# hot-plate_heater_v1_0.net
KiCad netlist of a schematic drawn in EAGLE
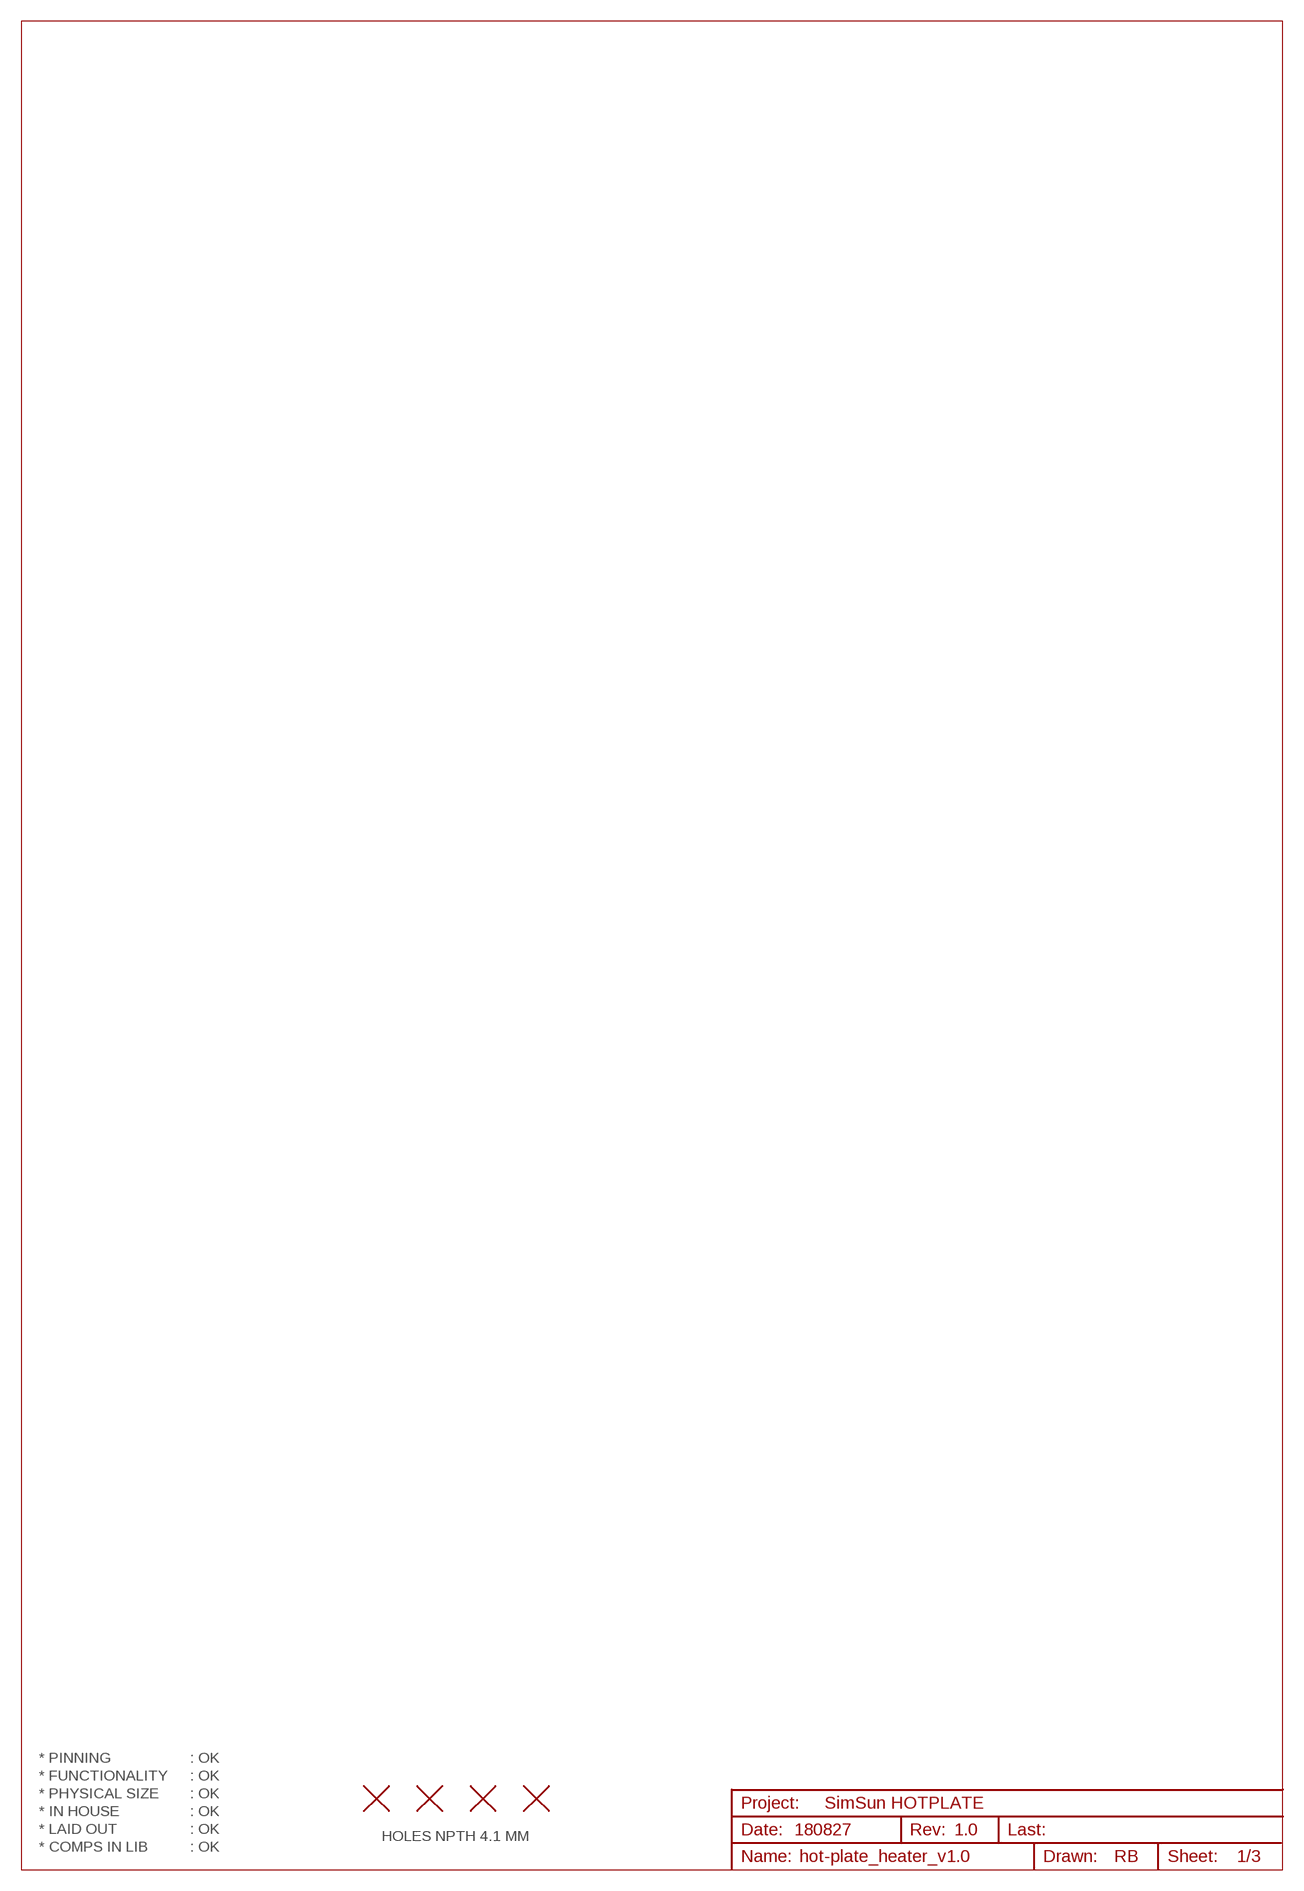
[diagram p0: schematic, sheet 1]
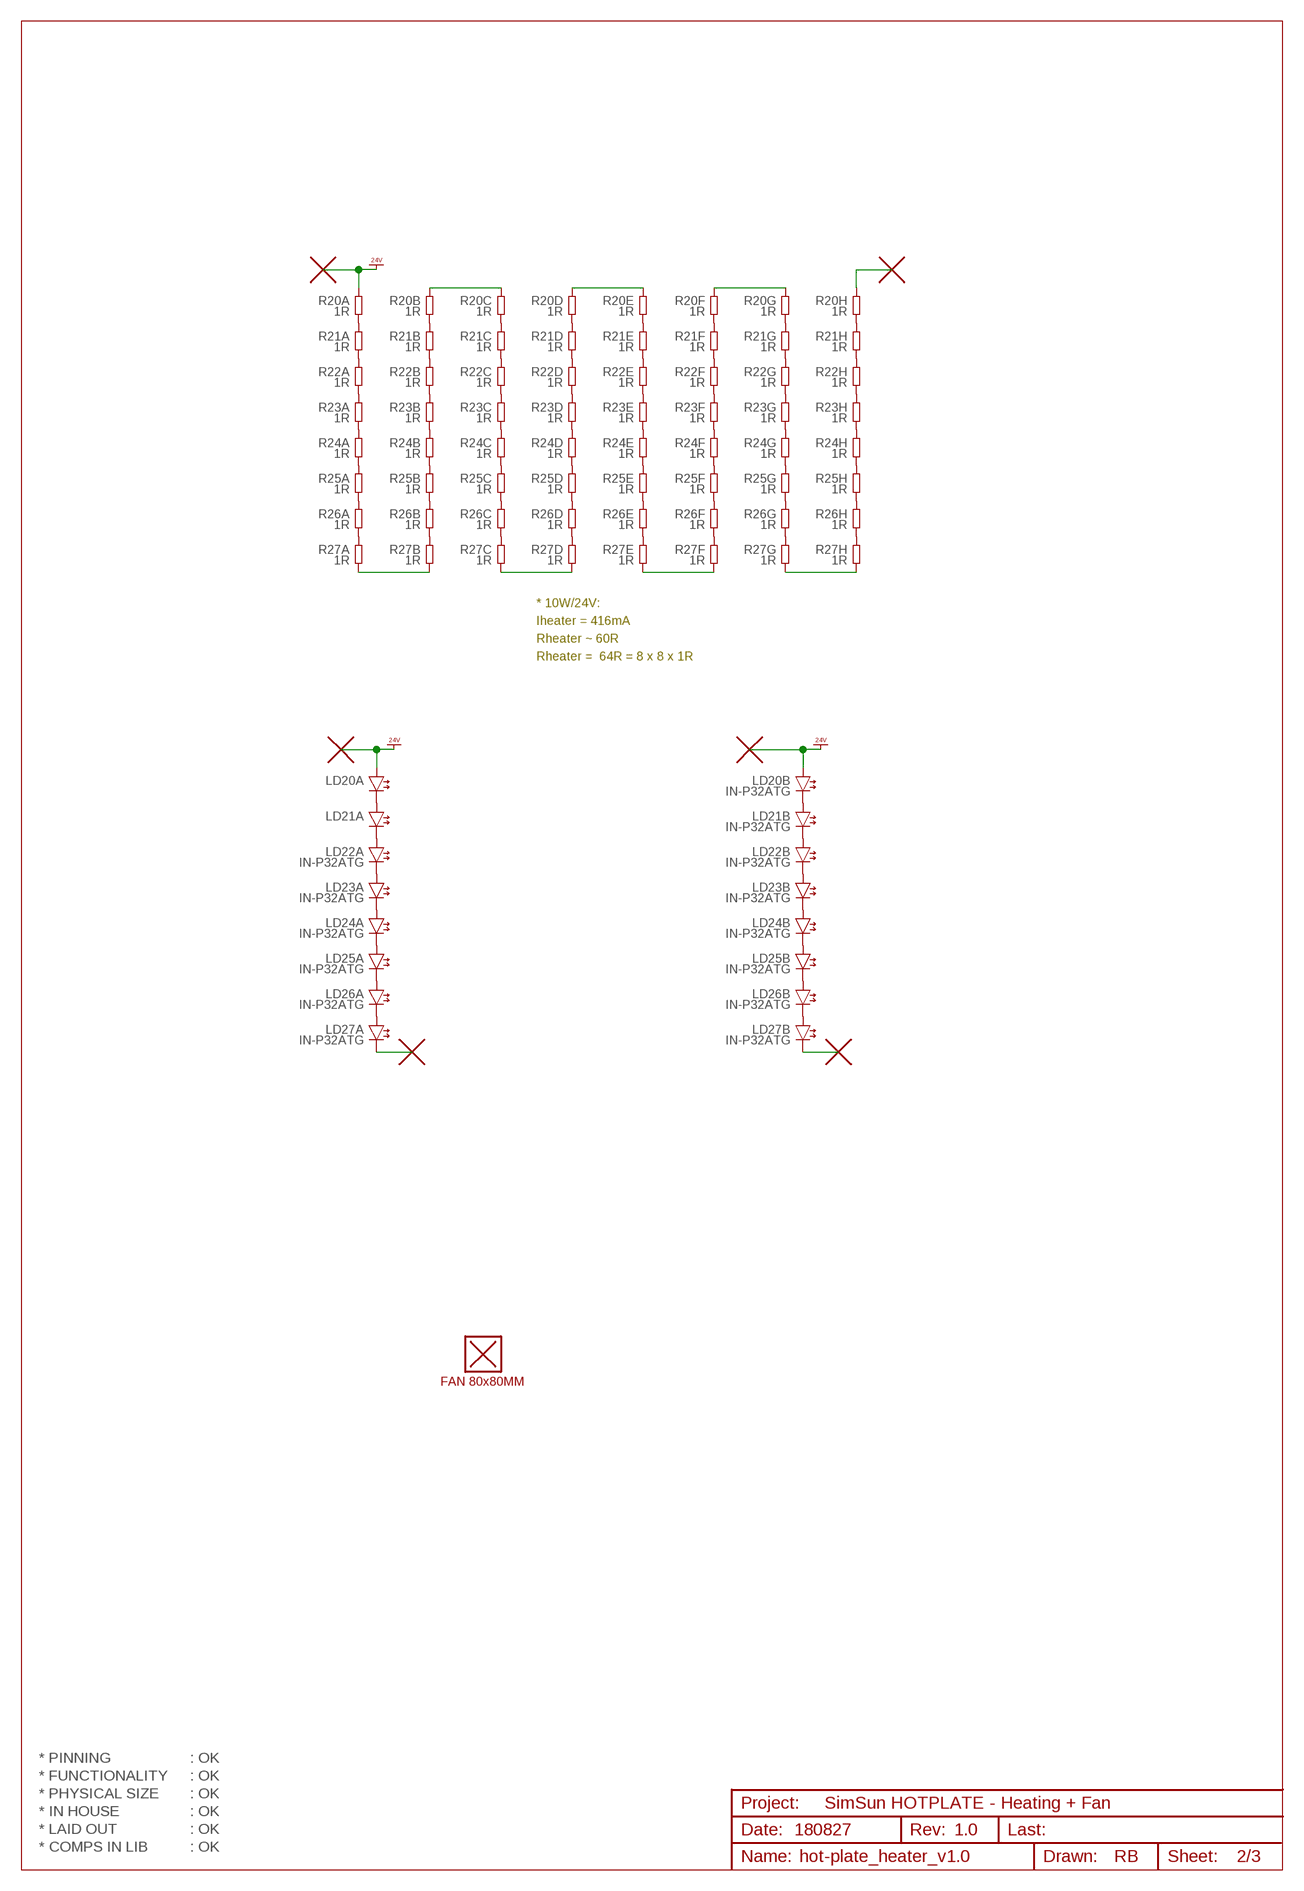
[diagram p1: schematic, sheet 2]
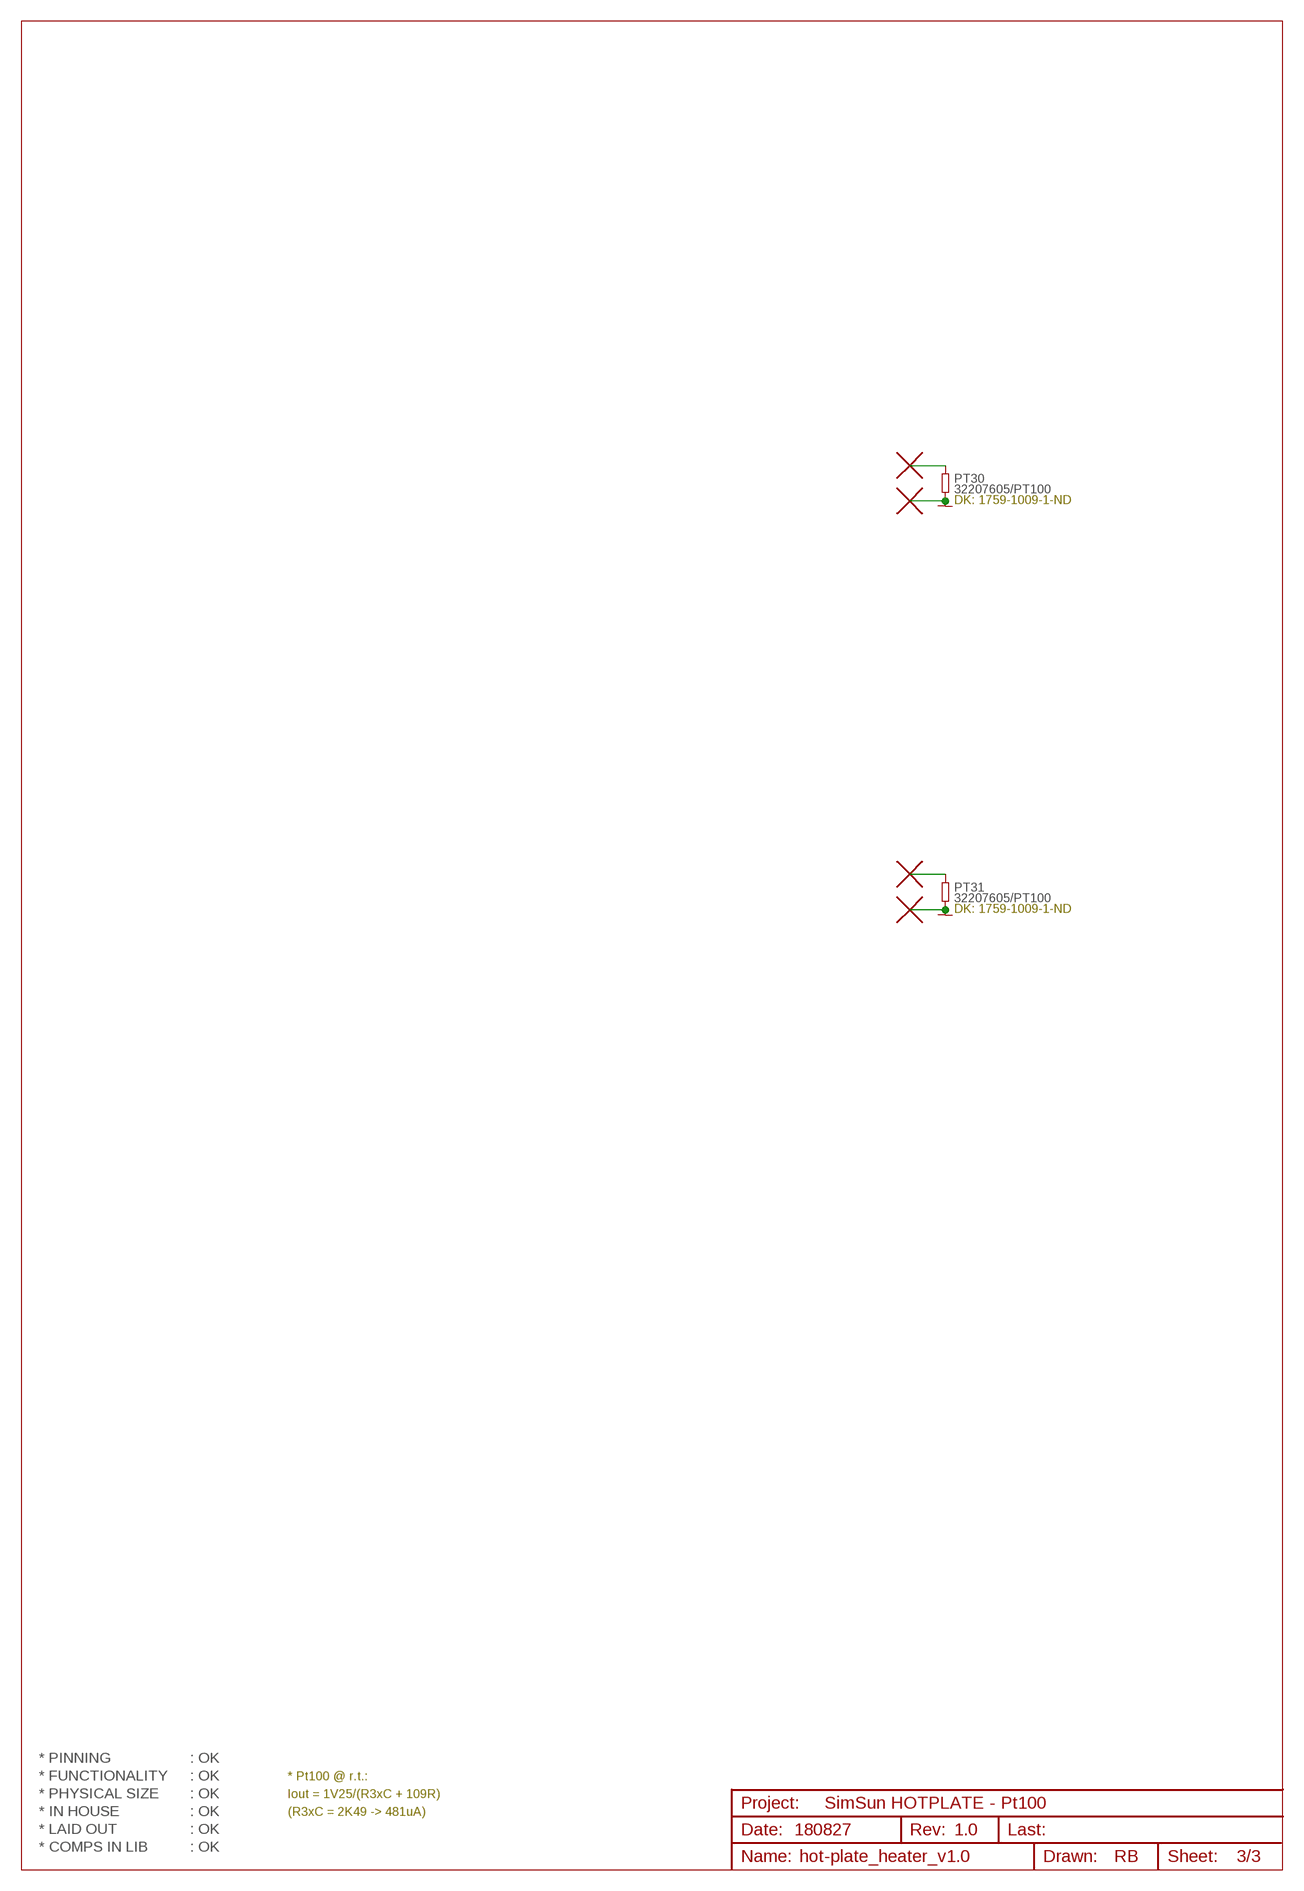
[diagram p2: schematic, sheet 3]

(export (version "E")
  (design (tool "Eeschema 10.0.6"))
  (components
    (comp (ref "H1")
      (value "HOLE_NPTH_4.1MM")
      (footprint "eagle-import:HOLE_NPTH_4.1MM")
      (libsource (lib "eagle-import") (part "HOLE_NPTH_4.1MM"))
    )
    (comp (ref "H2")
      (value "HOLE_NPTH_4.1MM")
      (footprint "eagle-import:HOLE_NPTH_4.1MM")
      (libsource (lib "eagle-import") (part "HOLE_NPTH_4.1MM"))
    )
    (comp (ref "H3")
      (value "HOLE_NPTH_4.1MM")
      (footprint "eagle-import:HOLE_NPTH_4.1MM")
      (libsource (lib "eagle-import") (part "HOLE_NPTH_4.1MM"))
    )
    (comp (ref "H4")
      (value "HOLE_NPTH_4.1MM")
      (footprint "eagle-import:HOLE_NPTH_4.1MM")
      (libsource (lib "eagle-import") (part "HOLE_NPTH_4.1MM"))
    )
    (comp (ref "H24")
      (value "PAD_ROUND_3.2MM")
      (footprint "eagle-import:PAD_ROUND_3.2MM")
      (libsource (lib "eagle-import") (part "PAD_ROUND_3.2MM"))
    )
    (comp (ref "H25")
      (value "PAD_ROUND_3.2MM")
      (footprint "eagle-import:PAD_ROUND_3.2MM")
      (libsource (lib "eagle-import") (part "PAD_ROUND_3.2MM"))
    )
    (comp (ref "H26")
      (value "PAD_ROUND_3.2MM")
      (footprint "eagle-import:PAD_ROUND_3.2MM")
      (libsource (lib "eagle-import") (part "PAD_ROUND_3.2MM"))
    )
    (comp (ref "H27")
      (value "PAD_ROUND_3.2MM")
      (footprint "eagle-import:PAD_ROUND_3.2MM")
      (libsource (lib "eagle-import") (part "PAD_ROUND_3.2MM"))
    )
    (comp (ref "PT30")
      (value "32207605/PT100")
      (footprint "eagle-import:RES0805")
      (libsource (lib "eagle-import") (part "RES0805"))
    )
    (comp (ref "PT31")
      (value "32207605/PT100")
      (footprint "eagle-import:RES0805")
      (libsource (lib "eagle-import") (part "RES0805"))
    )
    (comp (ref "H9")
      (value "FAN_80X80MM_SANYO_SANACE80")
      (footprint "eagle-import:FAN_80X80MM_SANYO_SANACE80")
      (libsource (lib "eagle-import") (part "FAN_80X80MM_SANYO_SANACE80"))
    )
    (comp (ref "H18")
      (value "PAD_ROUND_3.2MM")
      (footprint "eagle-import:PAD_ROUND_3.2MM")
      (libsource (lib "eagle-import") (part "PAD_ROUND_3.2MM"))
    )
    (comp (ref "H19")
      (value "PAD_ROUND_3.2MM")
      (footprint "eagle-import:PAD_ROUND_3.2MM")
      (libsource (lib "eagle-import") (part "PAD_ROUND_3.2MM"))
    )
    (comp (ref "H20")
      (value "PAD_ROUND_3.2MM")
      (footprint "eagle-import:PAD_ROUND_3.2MM")
      (libsource (lib "eagle-import") (part "PAD_ROUND_3.2MM"))
    )
    (comp (ref "H21")
      (value "PAD_ROUND_3.2MM")
      (footprint "eagle-import:PAD_ROUND_3.2MM")
      (libsource (lib "eagle-import") (part "PAD_ROUND_3.2MM"))
    )
    (comp (ref "H22")
      (value "PAD_ROUND_3.2MM")
      (footprint "eagle-import:PAD_ROUND_3.2MM")
      (libsource (lib "eagle-import") (part "PAD_ROUND_3.2MM"))
    )
    (comp (ref "H23")
      (value "PAD_ROUND_3.2MM")
      (footprint "eagle-import:PAD_ROUND_3.2MM")
      (libsource (lib "eagle-import") (part "PAD_ROUND_3.2MM"))
    )
    (comp (ref "LD20A")
      (value "IN-P32ATG")
      (footprint "eagle-import:LED_SMD_PLCC2")
      (libsource (lib "eagle-import") (part "LED_SMD_PLCC2"))
    )
    (comp (ref "LD20B")
      (value "IN-P32ATG")
      (footprint "eagle-import:LED_SMD_PLCC2")
      (libsource (lib "eagle-import") (part "LED_SMD_PLCC2"))
    )
    (comp (ref "LD21A")
      (value "IN-P32ATG")
      (footprint "eagle-import:LED_SMD_PLCC2")
      (libsource (lib "eagle-import") (part "LED_SMD_PLCC2"))
    )
    (comp (ref "LD21B")
      (value "IN-P32ATG")
      (footprint "eagle-import:LED_SMD_PLCC2")
      (libsource (lib "eagle-import") (part "LED_SMD_PLCC2"))
    )
    (comp (ref "LD22A")
      (value "IN-P32ATG")
      (footprint "eagle-import:LED_SMD_PLCC2")
      (libsource (lib "eagle-import") (part "LED_SMD_PLCC2"))
    )
    (comp (ref "LD22B")
      (value "IN-P32ATG")
      (footprint "eagle-import:LED_SMD_PLCC2")
      (libsource (lib "eagle-import") (part "LED_SMD_PLCC2"))
    )
    (comp (ref "LD23A")
      (value "IN-P32ATG")
      (footprint "eagle-import:LED_SMD_PLCC2")
      (libsource (lib "eagle-import") (part "LED_SMD_PLCC2"))
    )
    (comp (ref "LD23B")
      (value "IN-P32ATG")
      (footprint "eagle-import:LED_SMD_PLCC2")
      (libsource (lib "eagle-import") (part "LED_SMD_PLCC2"))
    )
    (comp (ref "LD24A")
      (value "IN-P32ATG")
      (footprint "eagle-import:LED_SMD_PLCC2")
      (libsource (lib "eagle-import") (part "LED_SMD_PLCC2"))
    )
    (comp (ref "LD24B")
      (value "IN-P32ATG")
      (footprint "eagle-import:LED_SMD_PLCC2")
      (libsource (lib "eagle-import") (part "LED_SMD_PLCC2"))
    )
    (comp (ref "LD25A")
      (value "IN-P32ATG")
      (footprint "eagle-import:LED_SMD_PLCC2")
      (libsource (lib "eagle-import") (part "LED_SMD_PLCC2"))
    )
    (comp (ref "LD25B")
      (value "IN-P32ATG")
      (footprint "eagle-import:LED_SMD_PLCC2")
      (libsource (lib "eagle-import") (part "LED_SMD_PLCC2"))
    )
    (comp (ref "LD26A")
      (value "IN-P32ATG")
      (footprint "eagle-import:LED_SMD_PLCC2")
      (libsource (lib "eagle-import") (part "LED_SMD_PLCC2"))
    )
    (comp (ref "LD26B")
      (value "IN-P32ATG")
      (footprint "eagle-import:LED_SMD_PLCC2")
      (libsource (lib "eagle-import") (part "LED_SMD_PLCC2"))
    )
    (comp (ref "LD27A")
      (value "IN-P32ATG")
      (footprint "eagle-import:LED_SMD_PLCC2")
      (libsource (lib "eagle-import") (part "LED_SMD_PLCC2"))
    )
    (comp (ref "LD27B")
      (value "IN-P32ATG")
      (footprint "eagle-import:LED_SMD_PLCC2")
      (libsource (lib "eagle-import") (part "LED_SMD_PLCC2"))
    )
    (comp (ref "R20A")
      (value "1R")
      (footprint "eagle-import:RES2512")
      (libsource (lib "eagle-import") (part "RES2512"))
    )
    (comp (ref "R20B")
      (value "1R")
      (footprint "eagle-import:RES2512")
      (libsource (lib "eagle-import") (part "RES2512"))
    )
    (comp (ref "R20C")
      (value "1R")
      (footprint "eagle-import:RES2512")
      (libsource (lib "eagle-import") (part "RES2512"))
    )
    (comp (ref "R20D")
      (value "1R")
      (footprint "eagle-import:RES2512")
      (libsource (lib "eagle-import") (part "RES2512"))
    )
    (comp (ref "R20E")
      (value "1R")
      (footprint "eagle-import:RES2512")
      (libsource (lib "eagle-import") (part "RES2512"))
    )
    (comp (ref "R20F")
      (value "1R")
      (footprint "eagle-import:RES2512")
      (libsource (lib "eagle-import") (part "RES2512"))
    )
    (comp (ref "R20G")
      (value "1R")
      (footprint "eagle-import:RES2512")
      (libsource (lib "eagle-import") (part "RES2512"))
    )
    (comp (ref "R20H")
      (value "1R")
      (footprint "eagle-import:RES2512")
      (libsource (lib "eagle-import") (part "RES2512"))
    )
    (comp (ref "R21A")
      (value "1R")
      (footprint "eagle-import:RES2512")
      (libsource (lib "eagle-import") (part "RES2512"))
    )
    (comp (ref "R21B")
      (value "1R")
      (footprint "eagle-import:RES2512")
      (libsource (lib "eagle-import") (part "RES2512"))
    )
    (comp (ref "R21C")
      (value "1R")
      (footprint "eagle-import:RES2512")
      (libsource (lib "eagle-import") (part "RES2512"))
    )
    (comp (ref "R21D")
      (value "1R")
      (footprint "eagle-import:RES2512")
      (libsource (lib "eagle-import") (part "RES2512"))
    )
    (comp (ref "R21E")
      (value "1R")
      (footprint "eagle-import:RES2512")
      (libsource (lib "eagle-import") (part "RES2512"))
    )
    (comp (ref "R21F")
      (value "1R")
      (footprint "eagle-import:RES2512")
      (libsource (lib "eagle-import") (part "RES2512"))
    )
    (comp (ref "R21G")
      (value "1R")
      (footprint "eagle-import:RES2512")
      (libsource (lib "eagle-import") (part "RES2512"))
    )
    (comp (ref "R21H")
      (value "1R")
      (footprint "eagle-import:RES2512")
      (libsource (lib "eagle-import") (part "RES2512"))
    )
    (comp (ref "R22A")
      (value "1R")
      (footprint "eagle-import:RES2512")
      (libsource (lib "eagle-import") (part "RES2512"))
    )
    (comp (ref "R22B")
      (value "1R")
      (footprint "eagle-import:RES2512")
      (libsource (lib "eagle-import") (part "RES2512"))
    )
    (comp (ref "R22C")
      (value "1R")
      (footprint "eagle-import:RES2512")
      (libsource (lib "eagle-import") (part "RES2512"))
    )
    (comp (ref "R22D")
      (value "1R")
      (footprint "eagle-import:RES2512")
      (libsource (lib "eagle-import") (part "RES2512"))
    )
    (comp (ref "R22E")
      (value "1R")
      (footprint "eagle-import:RES2512")
      (libsource (lib "eagle-import") (part "RES2512"))
    )
    (comp (ref "R22F")
      (value "1R")
      (footprint "eagle-import:RES2512")
      (libsource (lib "eagle-import") (part "RES2512"))
    )
    (comp (ref "R22G")
      (value "1R")
      (footprint "eagle-import:RES2512")
      (libsource (lib "eagle-import") (part "RES2512"))
    )
    (comp (ref "R22H")
      (value "1R")
      (footprint "eagle-import:RES2512")
      (libsource (lib "eagle-import") (part "RES2512"))
    )
    (comp (ref "R23A")
      (value "1R")
      (footprint "eagle-import:RES2512")
      (libsource (lib "eagle-import") (part "RES2512"))
    )
    (comp (ref "R23B")
      (value "1R")
      (footprint "eagle-import:RES2512")
      (libsource (lib "eagle-import") (part "RES2512"))
    )
    (comp (ref "R23C")
      (value "1R")
      (footprint "eagle-import:RES2512")
      (libsource (lib "eagle-import") (part "RES2512"))
    )
    (comp (ref "R23D")
      (value "1R")
      (footprint "eagle-import:RES2512")
      (libsource (lib "eagle-import") (part "RES2512"))
    )
    (comp (ref "R23E")
      (value "1R")
      (footprint "eagle-import:RES2512")
      (libsource (lib "eagle-import") (part "RES2512"))
    )
    (comp (ref "R23F")
      (value "1R")
      (footprint "eagle-import:RES2512")
      (libsource (lib "eagle-import") (part "RES2512"))
    )
    (comp (ref "R23G")
      (value "1R")
      (footprint "eagle-import:RES2512")
      (libsource (lib "eagle-import") (part "RES2512"))
    )
    (comp (ref "R23H")
      (value "1R")
      (footprint "eagle-import:RES2512")
      (libsource (lib "eagle-import") (part "RES2512"))
    )
    (comp (ref "R24A")
      (value "1R")
      (footprint "eagle-import:RES2512")
      (libsource (lib "eagle-import") (part "RES2512"))
    )
    (comp (ref "R24B")
      (value "1R")
      (footprint "eagle-import:RES2512")
      (libsource (lib "eagle-import") (part "RES2512"))
    )
    (comp (ref "R24C")
      (value "1R")
      (footprint "eagle-import:RES2512")
      (libsource (lib "eagle-import") (part "RES2512"))
    )
    (comp (ref "R24D")
      (value "1R")
      (footprint "eagle-import:RES2512")
      (libsource (lib "eagle-import") (part "RES2512"))
    )
    (comp (ref "R24E")
      (value "1R")
      (footprint "eagle-import:RES2512")
      (libsource (lib "eagle-import") (part "RES2512"))
    )
    (comp (ref "R24F")
      (value "1R")
      (footprint "eagle-import:RES2512")
      (libsource (lib "eagle-import") (part "RES2512"))
    )
    (comp (ref "R24G")
      (value "1R")
      (footprint "eagle-import:RES2512")
      (libsource (lib "eagle-import") (part "RES2512"))
    )
    (comp (ref "R24H")
      (value "1R")
      (footprint "eagle-import:RES2512")
      (libsource (lib "eagle-import") (part "RES2512"))
    )
    (comp (ref "R25A")
      (value "1R")
      (footprint "eagle-import:RES2512")
      (libsource (lib "eagle-import") (part "RES2512"))
    )
    (comp (ref "R25B")
      (value "1R")
      (footprint "eagle-import:RES2512")
      (libsource (lib "eagle-import") (part "RES2512"))
    )
    (comp (ref "R25C")
      (value "1R")
      (footprint "eagle-import:RES2512")
      (libsource (lib "eagle-import") (part "RES2512"))
    )
    (comp (ref "R25D")
      (value "1R")
      (footprint "eagle-import:RES2512")
      (libsource (lib "eagle-import") (part "RES2512"))
    )
    (comp (ref "R25E")
      (value "1R")
      (footprint "eagle-import:RES2512")
      (libsource (lib "eagle-import") (part "RES2512"))
    )
    (comp (ref "R25F")
      (value "1R")
      (footprint "eagle-import:RES2512")
      (libsource (lib "eagle-import") (part "RES2512"))
    )
    (comp (ref "R25G")
      (value "1R")
      (footprint "eagle-import:RES2512")
      (libsource (lib "eagle-import") (part "RES2512"))
    )
    (comp (ref "R25H")
      (value "1R")
      (footprint "eagle-import:RES2512")
      (libsource (lib "eagle-import") (part "RES2512"))
    )
    (comp (ref "R26A")
      (value "1R")
      (footprint "eagle-import:RES2512")
      (libsource (lib "eagle-import") (part "RES2512"))
    )
    (comp (ref "R26B")
      (value "1R")
      (footprint "eagle-import:RES2512")
      (libsource (lib "eagle-import") (part "RES2512"))
    )
    (comp (ref "R26C")
      (value "1R")
      (footprint "eagle-import:RES2512")
      (libsource (lib "eagle-import") (part "RES2512"))
    )
    (comp (ref "R26D")
      (value "1R")
      (footprint "eagle-import:RES2512")
      (libsource (lib "eagle-import") (part "RES2512"))
    )
    (comp (ref "R26E")
      (value "1R")
      (footprint "eagle-import:RES2512")
      (libsource (lib "eagle-import") (part "RES2512"))
    )
    (comp (ref "R26F")
      (value "1R")
      (footprint "eagle-import:RES2512")
      (libsource (lib "eagle-import") (part "RES2512"))
    )
    (comp (ref "R26G")
      (value "1R")
      (footprint "eagle-import:RES2512")
      (libsource (lib "eagle-import") (part "RES2512"))
    )
    (comp (ref "R26H")
      (value "1R")
      (footprint "eagle-import:RES2512")
      (libsource (lib "eagle-import") (part "RES2512"))
    )
    (comp (ref "R27A")
      (value "1R")
      (footprint "eagle-import:RES2512")
      (libsource (lib "eagle-import") (part "RES2512"))
    )
    (comp (ref "R27B")
      (value "1R")
      (footprint "eagle-import:RES2512")
      (libsource (lib "eagle-import") (part "RES2512"))
    )
    (comp (ref "R27C")
      (value "1R")
      (footprint "eagle-import:RES2512")
      (libsource (lib "eagle-import") (part "RES2512"))
    )
    (comp (ref "R27D")
      (value "1R")
      (footprint "eagle-import:RES2512")
      (libsource (lib "eagle-import") (part "RES2512"))
    )
    (comp (ref "R27E")
      (value "1R")
      (footprint "eagle-import:RES2512")
      (libsource (lib "eagle-import") (part "RES2512"))
    )
    (comp (ref "R27F")
      (value "1R")
      (footprint "eagle-import:RES2512")
      (libsource (lib "eagle-import") (part "RES2512"))
    )
    (comp (ref "R27G")
      (value "1R")
      (footprint "eagle-import:RES2512")
      (libsource (lib "eagle-import") (part "RES2512"))
    )
    (comp (ref "R27H")
      (value "1R")
      (footprint "eagle-import:RES2512")
      (libsource (lib "eagle-import") (part "RES2512"))
    )
  )
  (nets
    (net (code "1") (name "GND") (class "Default")
      (node (ref "H25") (pin "P") (pinfunction "P_P") (pintype "bidirectional"))
      (node (ref "H27") (pin "P") (pinfunction "P_P") (pintype "bidirectional"))
      (node (ref "PT30") (pin "2") (pinfunction "2_2") (pintype "passive"))
      (node (ref "PT31") (pin "2") (pinfunction "2_2") (pintype "passive"))
    )
    (net (code "2") (name "Net-(H19-PadP)") (class "Default")
      (node (ref "H19") (pin "P") (pinfunction "P_P") (pintype "bidirectional"))
      (node (ref "R20H") (pin "1") (pinfunction "1_1") (pintype "passive"))
    )
    (net (code "3") (name "Net-(H24-PadP)") (class "Default")
      (node (ref "H24") (pin "P") (pinfunction "P_P") (pintype "bidirectional"))
      (node (ref "PT30") (pin "1") (pinfunction "1_1") (pintype "passive"))
    )
    (net (code "4") (name "Net-(H26-PadP)") (class "Default")
      (node (ref "H26") (pin "P") (pinfunction "P_P") (pintype "bidirectional"))
      (node (ref "PT31") (pin "1") (pinfunction "1_1") (pintype "passive"))
    )
    (net (code "5") (name "Net-(LD20A--)") (class "Default")
      (node (ref "LD20A") (pin "C") (pinfunction "-_C") (pintype "passive"))
      (node (ref "LD21A") (pin "A") (pinfunction "+_A") (pintype "passive"))
    )
    (net (code "6") (name "Net-(LD20B--)") (class "Default")
      (node (ref "LD20B") (pin "C") (pinfunction "-_C") (pintype "passive"))
      (node (ref "LD21B") (pin "A") (pinfunction "+_A") (pintype "passive"))
    )
    (net (code "7") (name "Net-(LD21A--)") (class "Default")
      (node (ref "LD21A") (pin "C") (pinfunction "-_C") (pintype "passive"))
      (node (ref "LD22A") (pin "A") (pinfunction "+_A") (pintype "passive"))
    )
    (net (code "8") (name "Net-(LD21B--)") (class "Default")
      (node (ref "LD21B") (pin "C") (pinfunction "-_C") (pintype "passive"))
      (node (ref "LD22B") (pin "A") (pinfunction "+_A") (pintype "passive"))
    )
    (net (code "9") (name "Net-(LD22A--)") (class "Default")
      (node (ref "LD22A") (pin "C") (pinfunction "-_C") (pintype "passive"))
      (node (ref "LD23A") (pin "A") (pinfunction "+_A") (pintype "passive"))
    )
    (net (code "10") (name "Net-(LD22B--)") (class "Default")
      (node (ref "LD22B") (pin "C") (pinfunction "-_C") (pintype "passive"))
      (node (ref "LD23B") (pin "A") (pinfunction "+_A") (pintype "passive"))
    )
    (net (code "11") (name "Net-(LD23A--)") (class "Default")
      (node (ref "LD23A") (pin "C") (pinfunction "-_C") (pintype "passive"))
      (node (ref "LD24A") (pin "A") (pinfunction "+_A") (pintype "passive"))
    )
    (net (code "12") (name "Net-(LD23B--)") (class "Default")
      (node (ref "LD23B") (pin "C") (pinfunction "-_C") (pintype "passive"))
      (node (ref "LD24B") (pin "A") (pinfunction "+_A") (pintype "passive"))
    )
    (net (code "13") (name "Net-(LD24A--)") (class "Default")
      (node (ref "LD24A") (pin "C") (pinfunction "-_C") (pintype "passive"))
      (node (ref "LD25A") (pin "A") (pinfunction "+_A") (pintype "passive"))
    )
    (net (code "14") (name "Net-(LD24B--)") (class "Default")
      (node (ref "LD24B") (pin "C") (pinfunction "-_C") (pintype "passive"))
      (node (ref "LD25B") (pin "A") (pinfunction "+_A") (pintype "passive"))
    )
    (net (code "15") (name "Net-(LD25A--)") (class "Default")
      (node (ref "LD25A") (pin "C") (pinfunction "-_C") (pintype "passive"))
      (node (ref "LD26A") (pin "A") (pinfunction "+_A") (pintype "passive"))
    )
    (net (code "16") (name "Net-(LD25B--)") (class "Default")
      (node (ref "LD25B") (pin "C") (pinfunction "-_C") (pintype "passive"))
      (node (ref "LD26B") (pin "A") (pinfunction "+_A") (pintype "passive"))
    )
    (net (code "17") (name "Net-(LD26A--)") (class "Default")
      (node (ref "LD26A") (pin "C") (pinfunction "-_C") (pintype "passive"))
      (node (ref "LD27A") (pin "A") (pinfunction "+_A") (pintype "passive"))
    )
    (net (code "18") (name "Net-(LD26B--)") (class "Default")
      (node (ref "LD26B") (pin "C") (pinfunction "-_C") (pintype "passive"))
      (node (ref "LD27B") (pin "A") (pinfunction "+_A") (pintype "passive"))
    )
    (net (code "19") (name "Net-(LD27A--)") (class "Default")
      (node (ref "H22") (pin "P") (pinfunction "P_P") (pintype "bidirectional"))
      (node (ref "LD27A") (pin "C") (pinfunction "-_C") (pintype "passive"))
    )
    (net (code "20") (name "Net-(LD27B--)") (class "Default")
      (node (ref "H23") (pin "P") (pinfunction "P_P") (pintype "bidirectional"))
      (node (ref "LD27B") (pin "C") (pinfunction "-_C") (pintype "passive"))
    )
    (net (code "21") (name "Net-(R20A-Pad2)") (class "Default")
      (node (ref "R20A") (pin "2") (pinfunction "2_2") (pintype "passive"))
      (node (ref "R21A") (pin "1") (pinfunction "1_1") (pintype "passive"))
    )
    (net (code "22") (name "Net-(R20B-Pad1)") (class "Default")
      (node (ref "R20B") (pin "1") (pinfunction "1_1") (pintype "passive"))
      (node (ref "R20C") (pin "1") (pinfunction "1_1") (pintype "passive"))
    )
    (net (code "23") (name "Net-(R20B-Pad2)") (class "Default")
      (node (ref "R20B") (pin "2") (pinfunction "2_2") (pintype "passive"))
      (node (ref "R21B") (pin "1") (pinfunction "1_1") (pintype "passive"))
    )
    (net (code "24") (name "Net-(R20C-Pad2)") (class "Default")
      (node (ref "R20C") (pin "2") (pinfunction "2_2") (pintype "passive"))
      (node (ref "R21C") (pin "1") (pinfunction "1_1") (pintype "passive"))
    )
    (net (code "25") (name "Net-(R20D-Pad1)") (class "Default")
      (node (ref "R20D") (pin "1") (pinfunction "1_1") (pintype "passive"))
      (node (ref "R20E") (pin "1") (pinfunction "1_1") (pintype "passive"))
    )
    (net (code "26") (name "Net-(R20D-Pad2)") (class "Default")
      (node (ref "R20D") (pin "2") (pinfunction "2_2") (pintype "passive"))
      (node (ref "R21D") (pin "1") (pinfunction "1_1") (pintype "passive"))
    )
    (net (code "27") (name "Net-(R20E-Pad2)") (class "Default")
      (node (ref "R20E") (pin "2") (pinfunction "2_2") (pintype "passive"))
      (node (ref "R21E") (pin "1") (pinfunction "1_1") (pintype "passive"))
    )
    (net (code "28") (name "Net-(R20F-Pad1)") (class "Default")
      (node (ref "R20F") (pin "1") (pinfunction "1_1") (pintype "passive"))
      (node (ref "R20G") (pin "1") (pinfunction "1_1") (pintype "passive"))
    )
    (net (code "29") (name "Net-(R20F-Pad2)") (class "Default")
      (node (ref "R20F") (pin "2") (pinfunction "2_2") (pintype "passive"))
      (node (ref "R21F") (pin "1") (pinfunction "1_1") (pintype "passive"))
    )
    (net (code "30") (name "Net-(R20G-Pad2)") (class "Default")
      (node (ref "R20G") (pin "2") (pinfunction "2_2") (pintype "passive"))
      (node (ref "R21G") (pin "1") (pinfunction "1_1") (pintype "passive"))
    )
    (net (code "31") (name "Net-(R20H-Pad2)") (class "Default")
      (node (ref "R20H") (pin "2") (pinfunction "2_2") (pintype "passive"))
      (node (ref "R21H") (pin "1") (pinfunction "1_1") (pintype "passive"))
    )
    (net (code "32") (name "Net-(R21A-Pad2)") (class "Default")
      (node (ref "R21A") (pin "2") (pinfunction "2_2") (pintype "passive"))
      (node (ref "R22A") (pin "1") (pinfunction "1_1") (pintype "passive"))
    )
    (net (code "33") (name "Net-(R21B-Pad2)") (class "Default")
      (node (ref "R21B") (pin "2") (pinfunction "2_2") (pintype "passive"))
      (node (ref "R22B") (pin "1") (pinfunction "1_1") (pintype "passive"))
    )
    (net (code "34") (name "Net-(R21C-Pad2)") (class "Default")
      (node (ref "R21C") (pin "2") (pinfunction "2_2") (pintype "passive"))
      (node (ref "R22C") (pin "1") (pinfunction "1_1") (pintype "passive"))
    )
    (net (code "35") (name "Net-(R21D-Pad2)") (class "Default")
      (node (ref "R21D") (pin "2") (pinfunction "2_2") (pintype "passive"))
      (node (ref "R22D") (pin "1") (pinfunction "1_1") (pintype "passive"))
    )
    (net (code "36") (name "Net-(R21E-Pad2)") (class "Default")
      (node (ref "R21E") (pin "2") (pinfunction "2_2") (pintype "passive"))
      (node (ref "R22E") (pin "1") (pinfunction "1_1") (pintype "passive"))
    )
    (net (code "37") (name "Net-(R21F-Pad2)") (class "Default")
      (node (ref "R21F") (pin "2") (pinfunction "2_2") (pintype "passive"))
      (node (ref "R22F") (pin "1") (pinfunction "1_1") (pintype "passive"))
    )
    (net (code "38") (name "Net-(R21G-Pad2)") (class "Default")
      (node (ref "R21G") (pin "2") (pinfunction "2_2") (pintype "passive"))
      (node (ref "R22G") (pin "1") (pinfunction "1_1") (pintype "passive"))
    )
    (net (code "39") (name "Net-(R21H-Pad2)") (class "Default")
      (node (ref "R21H") (pin "2") (pinfunction "2_2") (pintype "passive"))
      (node (ref "R22H") (pin "1") (pinfunction "1_1") (pintype "passive"))
    )
    (net (code "40") (name "Net-(R22A-Pad2)") (class "Default")
      (node (ref "R22A") (pin "2") (pinfunction "2_2") (pintype "passive"))
      (node (ref "R23A") (pin "1") (pinfunction "1_1") (pintype "passive"))
    )
    (net (code "41") (name "Net-(R22B-Pad2)") (class "Default")
      (node (ref "R22B") (pin "2") (pinfunction "2_2") (pintype "passive"))
      (node (ref "R23B") (pin "1") (pinfunction "1_1") (pintype "passive"))
    )
    (net (code "42") (name "Net-(R22C-Pad2)") (class "Default")
      (node (ref "R22C") (pin "2") (pinfunction "2_2") (pintype "passive"))
      (node (ref "R23C") (pin "1") (pinfunction "1_1") (pintype "passive"))
    )
    (net (code "43") (name "Net-(R22D-Pad2)") (class "Default")
      (node (ref "R22D") (pin "2") (pinfunction "2_2") (pintype "passive"))
      (node (ref "R23D") (pin "1") (pinfunction "1_1") (pintype "passive"))
    )
    (net (code "44") (name "Net-(R22E-Pad2)") (class "Default")
      (node (ref "R22E") (pin "2") (pinfunction "2_2") (pintype "passive"))
      (node (ref "R23E") (pin "1") (pinfunction "1_1") (pintype "passive"))
    )
    (net (code "45") (name "Net-(R22F-Pad2)") (class "Default")
      (node (ref "R22F") (pin "2") (pinfunction "2_2") (pintype "passive"))
      (node (ref "R23F") (pin "1") (pinfunction "1_1") (pintype "passive"))
    )
    (net (code "46") (name "Net-(R22G-Pad2)") (class "Default")
      (node (ref "R22G") (pin "2") (pinfunction "2_2") (pintype "passive"))
      (node (ref "R23G") (pin "1") (pinfunction "1_1") (pintype "passive"))
    )
    (net (code "47") (name "Net-(R22H-Pad2)") (class "Default")
      (node (ref "R22H") (pin "2") (pinfunction "2_2") (pintype "passive"))
      (node (ref "R23H") (pin "1") (pinfunction "1_1") (pintype "passive"))
    )
    (net (code "48") (name "Net-(R23A-Pad2)") (class "Default")
      (node (ref "R23A") (pin "2") (pinfunction "2_2") (pintype "passive"))
      (node (ref "R24A") (pin "1") (pinfunction "1_1") (pintype "passive"))
    )
    (net (code "49") (name "Net-(R23B-Pad2)") (class "Default")
      (node (ref "R23B") (pin "2") (pinfunction "2_2") (pintype "passive"))
      (node (ref "R24B") (pin "1") (pinfunction "1_1") (pintype "passive"))
    )
    (net (code "50") (name "Net-(R23C-Pad2)") (class "Default")
      (node (ref "R23C") (pin "2") (pinfunction "2_2") (pintype "passive"))
      (node (ref "R24C") (pin "1") (pinfunction "1_1") (pintype "passive"))
    )
    (net (code "51") (name "Net-(R23D-Pad2)") (class "Default")
      (node (ref "R23D") (pin "2") (pinfunction "2_2") (pintype "passive"))
      (node (ref "R24D") (pin "1") (pinfunction "1_1") (pintype "passive"))
    )
    (net (code "52") (name "Net-(R23E-Pad2)") (class "Default")
      (node (ref "R23E") (pin "2") (pinfunction "2_2") (pintype "passive"))
      (node (ref "R24E") (pin "1") (pinfunction "1_1") (pintype "passive"))
    )
    (net (code "53") (name "Net-(R23F-Pad2)") (class "Default")
      (node (ref "R23F") (pin "2") (pinfunction "2_2") (pintype "passive"))
      (node (ref "R24F") (pin "1") (pinfunction "1_1") (pintype "passive"))
    )
    (net (code "54") (name "Net-(R23G-Pad2)") (class "Default")
      (node (ref "R23G") (pin "2") (pinfunction "2_2") (pintype "passive"))
      (node (ref "R24G") (pin "1") (pinfunction "1_1") (pintype "passive"))
    )
    (net (code "55") (name "Net-(R23H-Pad2)") (class "Default")
      (node (ref "R23H") (pin "2") (pinfunction "2_2") (pintype "passive"))
      (node (ref "R24H") (pin "1") (pinfunction "1_1") (pintype "passive"))
    )
    (net (code "56") (name "Net-(R24A-Pad2)") (class "Default")
      (node (ref "R24A") (pin "2") (pinfunction "2_2") (pintype "passive"))
      (node (ref "R25A") (pin "1") (pinfunction "1_1") (pintype "passive"))
    )
    (net (code "57") (name "Net-(R24B-Pad2)") (class "Default")
      (node (ref "R24B") (pin "2") (pinfunction "2_2") (pintype "passive"))
      (node (ref "R25B") (pin "1") (pinfunction "1_1") (pintype "passive"))
    )
    (net (code "58") (name "Net-(R24C-Pad2)") (class "Default")
      (node (ref "R24C") (pin "2") (pinfunction "2_2") (pintype "passive"))
      (node (ref "R25C") (pin "1") (pinfunction "1_1") (pintype "passive"))
    )
    (net (code "59") (name "Net-(R24D-Pad2)") (class "Default")
      (node (ref "R24D") (pin "2") (pinfunction "2_2") (pintype "passive"))
      (node (ref "R25D") (pin "1") (pinfunction "1_1") (pintype "passive"))
    )
    (net (code "60") (name "Net-(R24E-Pad2)") (class "Default")
      (node (ref "R24E") (pin "2") (pinfunction "2_2") (pintype "passive"))
      (node (ref "R25E") (pin "1") (pinfunction "1_1") (pintype "passive"))
    )
    (net (code "61") (name "Net-(R24F-Pad2)") (class "Default")
      (node (ref "R24F") (pin "2") (pinfunction "2_2") (pintype "passive"))
      (node (ref "R25F") (pin "1") (pinfunction "1_1") (pintype "passive"))
    )
    (net (code "62") (name "Net-(R24G-Pad2)") (class "Default")
      (node (ref "R24G") (pin "2") (pinfunction "2_2") (pintype "passive"))
      (node (ref "R25G") (pin "1") (pinfunction "1_1") (pintype "passive"))
    )
    (net (code "63") (name "Net-(R24H-Pad2)") (class "Default")
      (node (ref "R24H") (pin "2") (pinfunction "2_2") (pintype "passive"))
      (node (ref "R25H") (pin "1") (pinfunction "1_1") (pintype "passive"))
    )
    (net (code "64") (name "Net-(R25A-Pad2)") (class "Default")
      (node (ref "R25A") (pin "2") (pinfunction "2_2") (pintype "passive"))
      (node (ref "R26A") (pin "1") (pinfunction "1_1") (pintype "passive"))
    )
    (net (code "65") (name "Net-(R25B-Pad2)") (class "Default")
      (node (ref "R25B") (pin "2") (pinfunction "2_2") (pintype "passive"))
      (node (ref "R26B") (pin "1") (pinfunction "1_1") (pintype "passive"))
    )
    (net (code "66") (name "Net-(R25C-Pad2)") (class "Default")
      (node (ref "R25C") (pin "2") (pinfunction "2_2") (pintype "passive"))
      (node (ref "R26C") (pin "1") (pinfunction "1_1") (pintype "passive"))
    )
    (net (code "67") (name "Net-(R25D-Pad2)") (class "Default")
      (node (ref "R25D") (pin "2") (pinfunction "2_2") (pintype "passive"))
      (node (ref "R26D") (pin "1") (pinfunction "1_1") (pintype "passive"))
    )
    (net (code "68") (name "Net-(R25E-Pad2)") (class "Default")
      (node (ref "R25E") (pin "2") (pinfunction "2_2") (pintype "passive"))
      (node (ref "R26E") (pin "1") (pinfunction "1_1") (pintype "passive"))
    )
    (net (code "69") (name "Net-(R25F-Pad2)") (class "Default")
      (node (ref "R25F") (pin "2") (pinfunction "2_2") (pintype "passive"))
      (node (ref "R26F") (pin "1") (pinfunction "1_1") (pintype "passive"))
    )
    (net (code "70") (name "Net-(R25G-Pad2)") (class "Default")
      (node (ref "R25G") (pin "2") (pinfunction "2_2") (pintype "passive"))
      (node (ref "R26G") (pin "1") (pinfunction "1_1") (pintype "passive"))
    )
    (net (code "71") (name "Net-(R25H-Pad2)") (class "Default")
      (node (ref "R25H") (pin "2") (pinfunction "2_2") (pintype "passive"))
      (node (ref "R26H") (pin "1") (pinfunction "1_1") (pintype "passive"))
    )
    (net (code "72") (name "Net-(R26A-Pad2)") (class "Default")
      (node (ref "R26A") (pin "2") (pinfunction "2_2") (pintype "passive"))
      (node (ref "R27A") (pin "1") (pinfunction "1_1") (pintype "passive"))
    )
    (net (code "73") (name "Net-(R26B-Pad2)") (class "Default")
      (node (ref "R26B") (pin "2") (pinfunction "2_2") (pintype "passive"))
      (node (ref "R27B") (pin "1") (pinfunction "1_1") (pintype "passive"))
    )
    (net (code "74") (name "Net-(R26C-Pad2)") (class "Default")
      (node (ref "R26C") (pin "2") (pinfunction "2_2") (pintype "passive"))
      (node (ref "R27C") (pin "1") (pinfunction "1_1") (pintype "passive"))
    )
    (net (code "75") (name "Net-(R26D-Pad2)") (class "Default")
      (node (ref "R26D") (pin "2") (pinfunction "2_2") (pintype "passive"))
      (node (ref "R27D") (pin "1") (pinfunction "1_1") (pintype "passive"))
    )
    (net (code "76") (name "Net-(R26E-Pad2)") (class "Default")
      (node (ref "R26E") (pin "2") (pinfunction "2_2") (pintype "passive"))
      (node (ref "R27E") (pin "1") (pinfunction "1_1") (pintype "passive"))
    )
    (net (code "77") (name "Net-(R26F-Pad2)") (class "Default")
      (node (ref "R26F") (pin "2") (pinfunction "2_2") (pintype "passive"))
      (node (ref "R27F") (pin "1") (pinfunction "1_1") (pintype "passive"))
    )
    (net (code "78") (name "Net-(R26G-Pad2)") (class "Default")
      (node (ref "R26G") (pin "2") (pinfunction "2_2") (pintype "passive"))
      (node (ref "R27G") (pin "1") (pinfunction "1_1") (pintype "passive"))
    )
    (net (code "79") (name "Net-(R26H-Pad2)") (class "Default")
      (node (ref "R26H") (pin "2") (pinfunction "2_2") (pintype "passive"))
      (node (ref "R27H") (pin "1") (pinfunction "1_1") (pintype "passive"))
    )
    (net (code "80") (name "Net-(R27A-Pad2)") (class "Default")
      (node (ref "R27A") (pin "2") (pinfunction "2_2") (pintype "passive"))
      (node (ref "R27B") (pin "2") (pinfunction "2_2") (pintype "passive"))
    )
    (net (code "81") (name "Net-(R27C-Pad2)") (class "Default")
      (node (ref "R27C") (pin "2") (pinfunction "2_2") (pintype "passive"))
      (node (ref "R27D") (pin "2") (pinfunction "2_2") (pintype "passive"))
    )
    (net (code "82") (name "Net-(R27E-Pad2)") (class "Default")
      (node (ref "R27E") (pin "2") (pinfunction "2_2") (pintype "passive"))
      (node (ref "R27F") (pin "2") (pinfunction "2_2") (pintype "passive"))
    )
    (net (code "83") (name "Net-(R27G-Pad2)") (class "Default")
      (node (ref "R27G") (pin "2") (pinfunction "2_2") (pintype "passive"))
      (node (ref "R27H") (pin "2") (pinfunction "2_2") (pintype "passive"))
    )
    (net (code "84") (name "VDD_24V") (class "Default")
      (node (ref "H18") (pin "P") (pinfunction "P_P") (pintype "bidirectional"))
      (node (ref "H20") (pin "P") (pinfunction "P_P") (pintype "bidirectional"))
      (node (ref "H21") (pin "P") (pinfunction "P_P") (pintype "bidirectional"))
      (node (ref "LD20A") (pin "A") (pinfunction "+_A") (pintype "passive"))
      (node (ref "LD20B") (pin "A") (pinfunction "+_A") (pintype "passive"))
      (node (ref "R20A") (pin "1") (pinfunction "1_1") (pintype "passive"))
    )
  )
)
